# SchemaPCB1.net
KiCad netlist of a schematic drawn in EAGLE
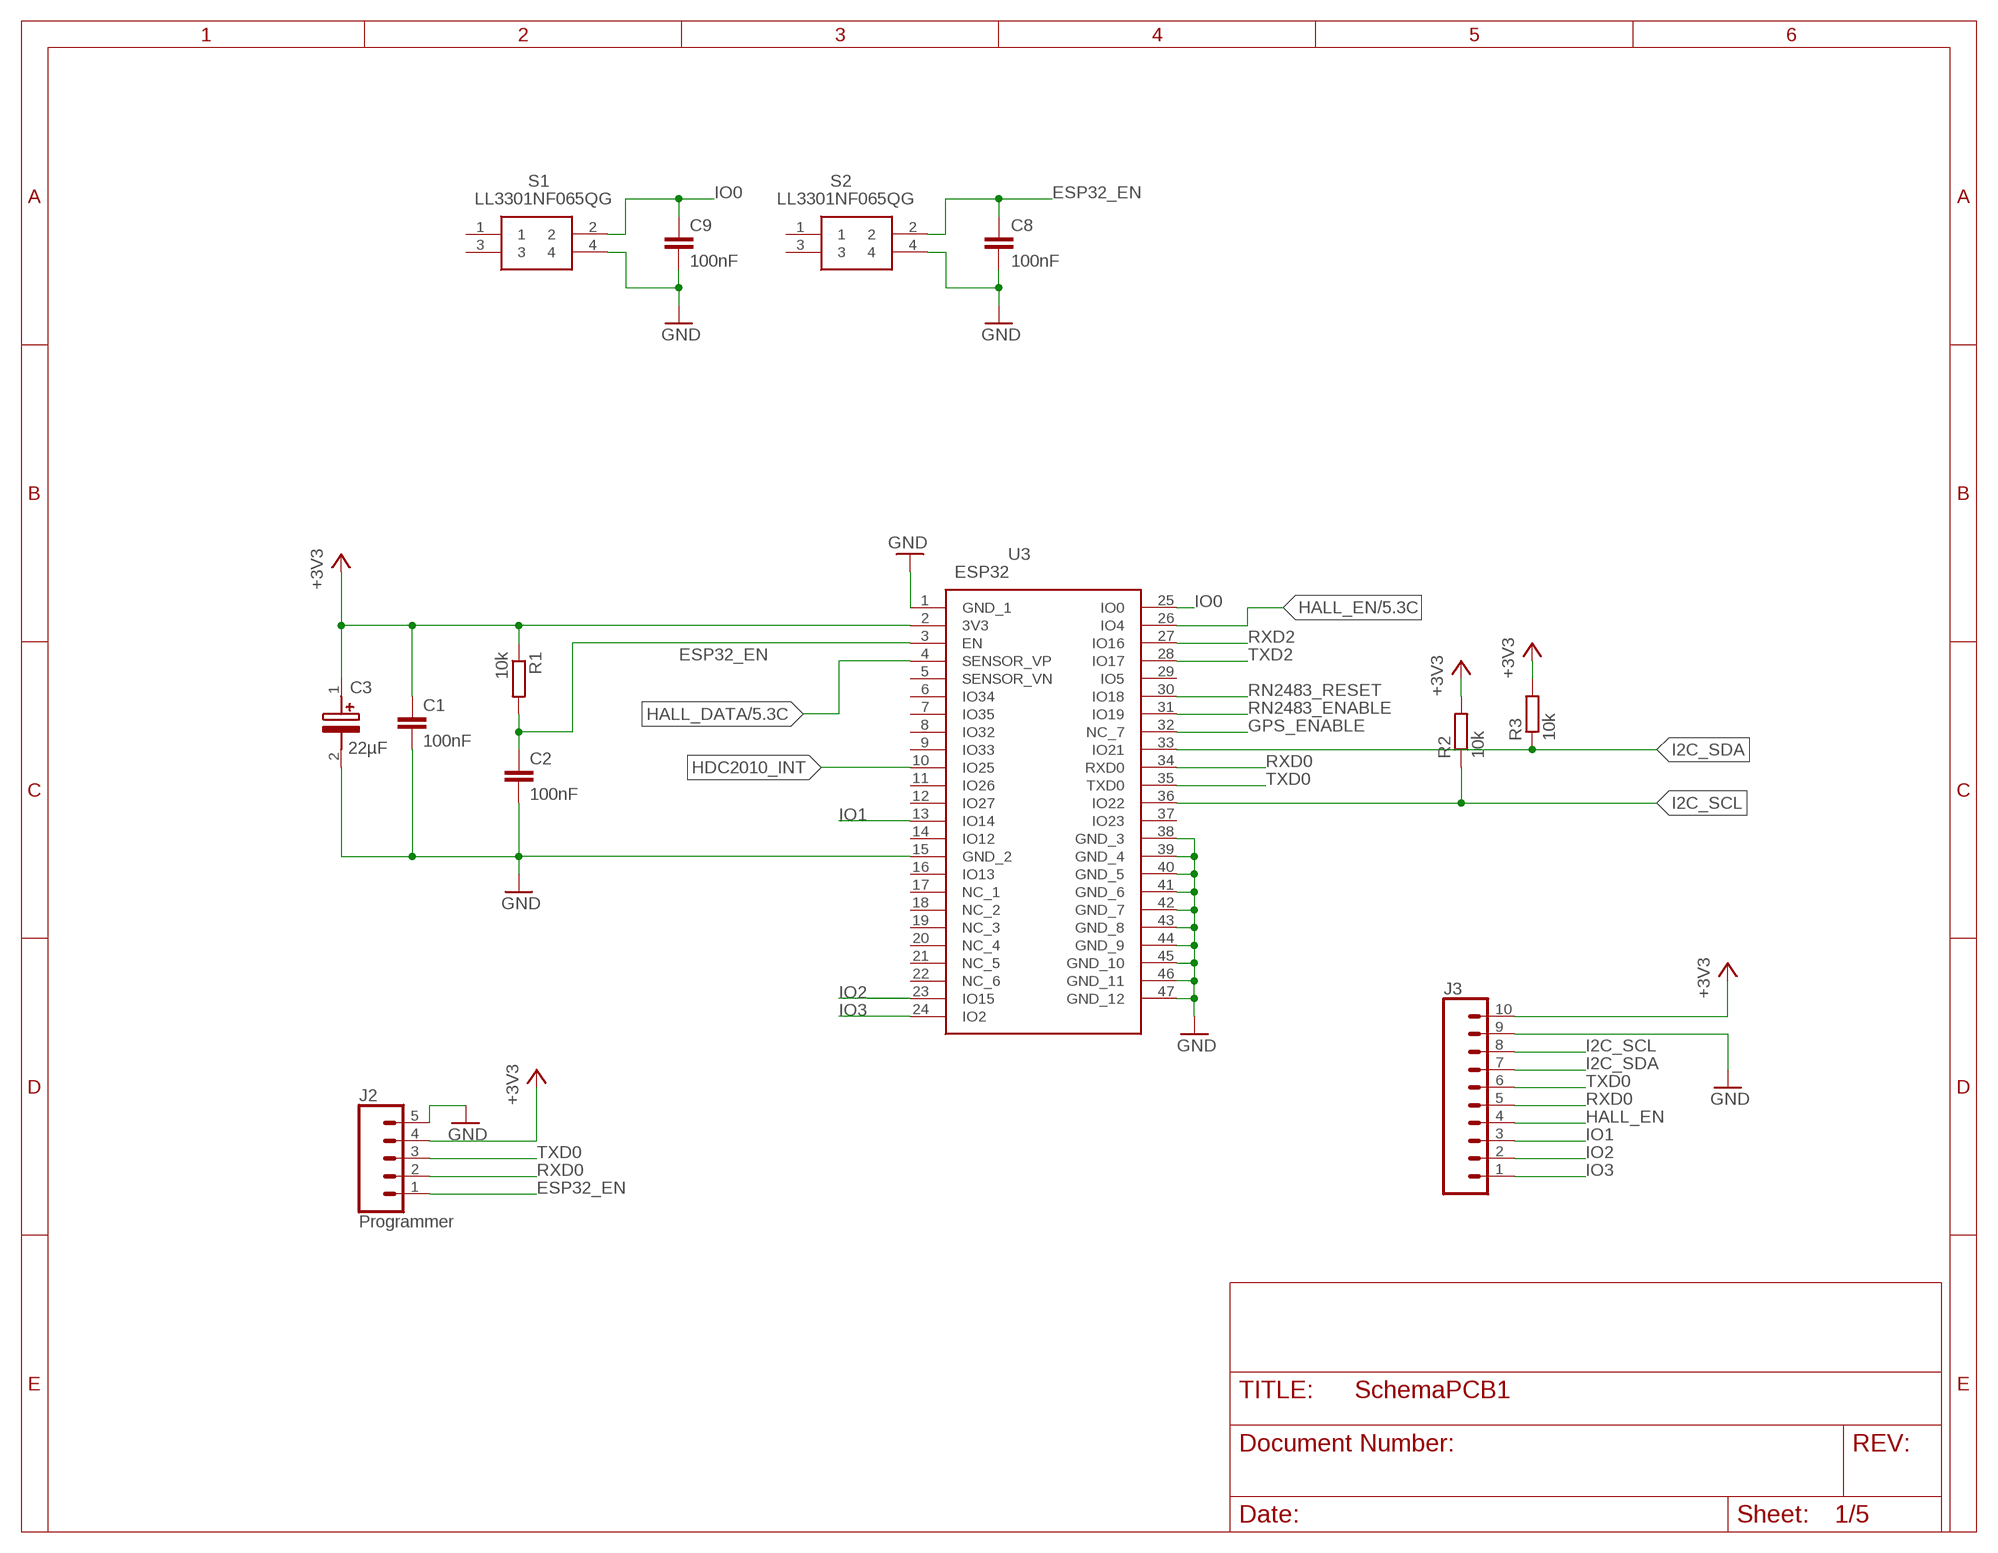
[diagram p0: schematic, sheet 1]
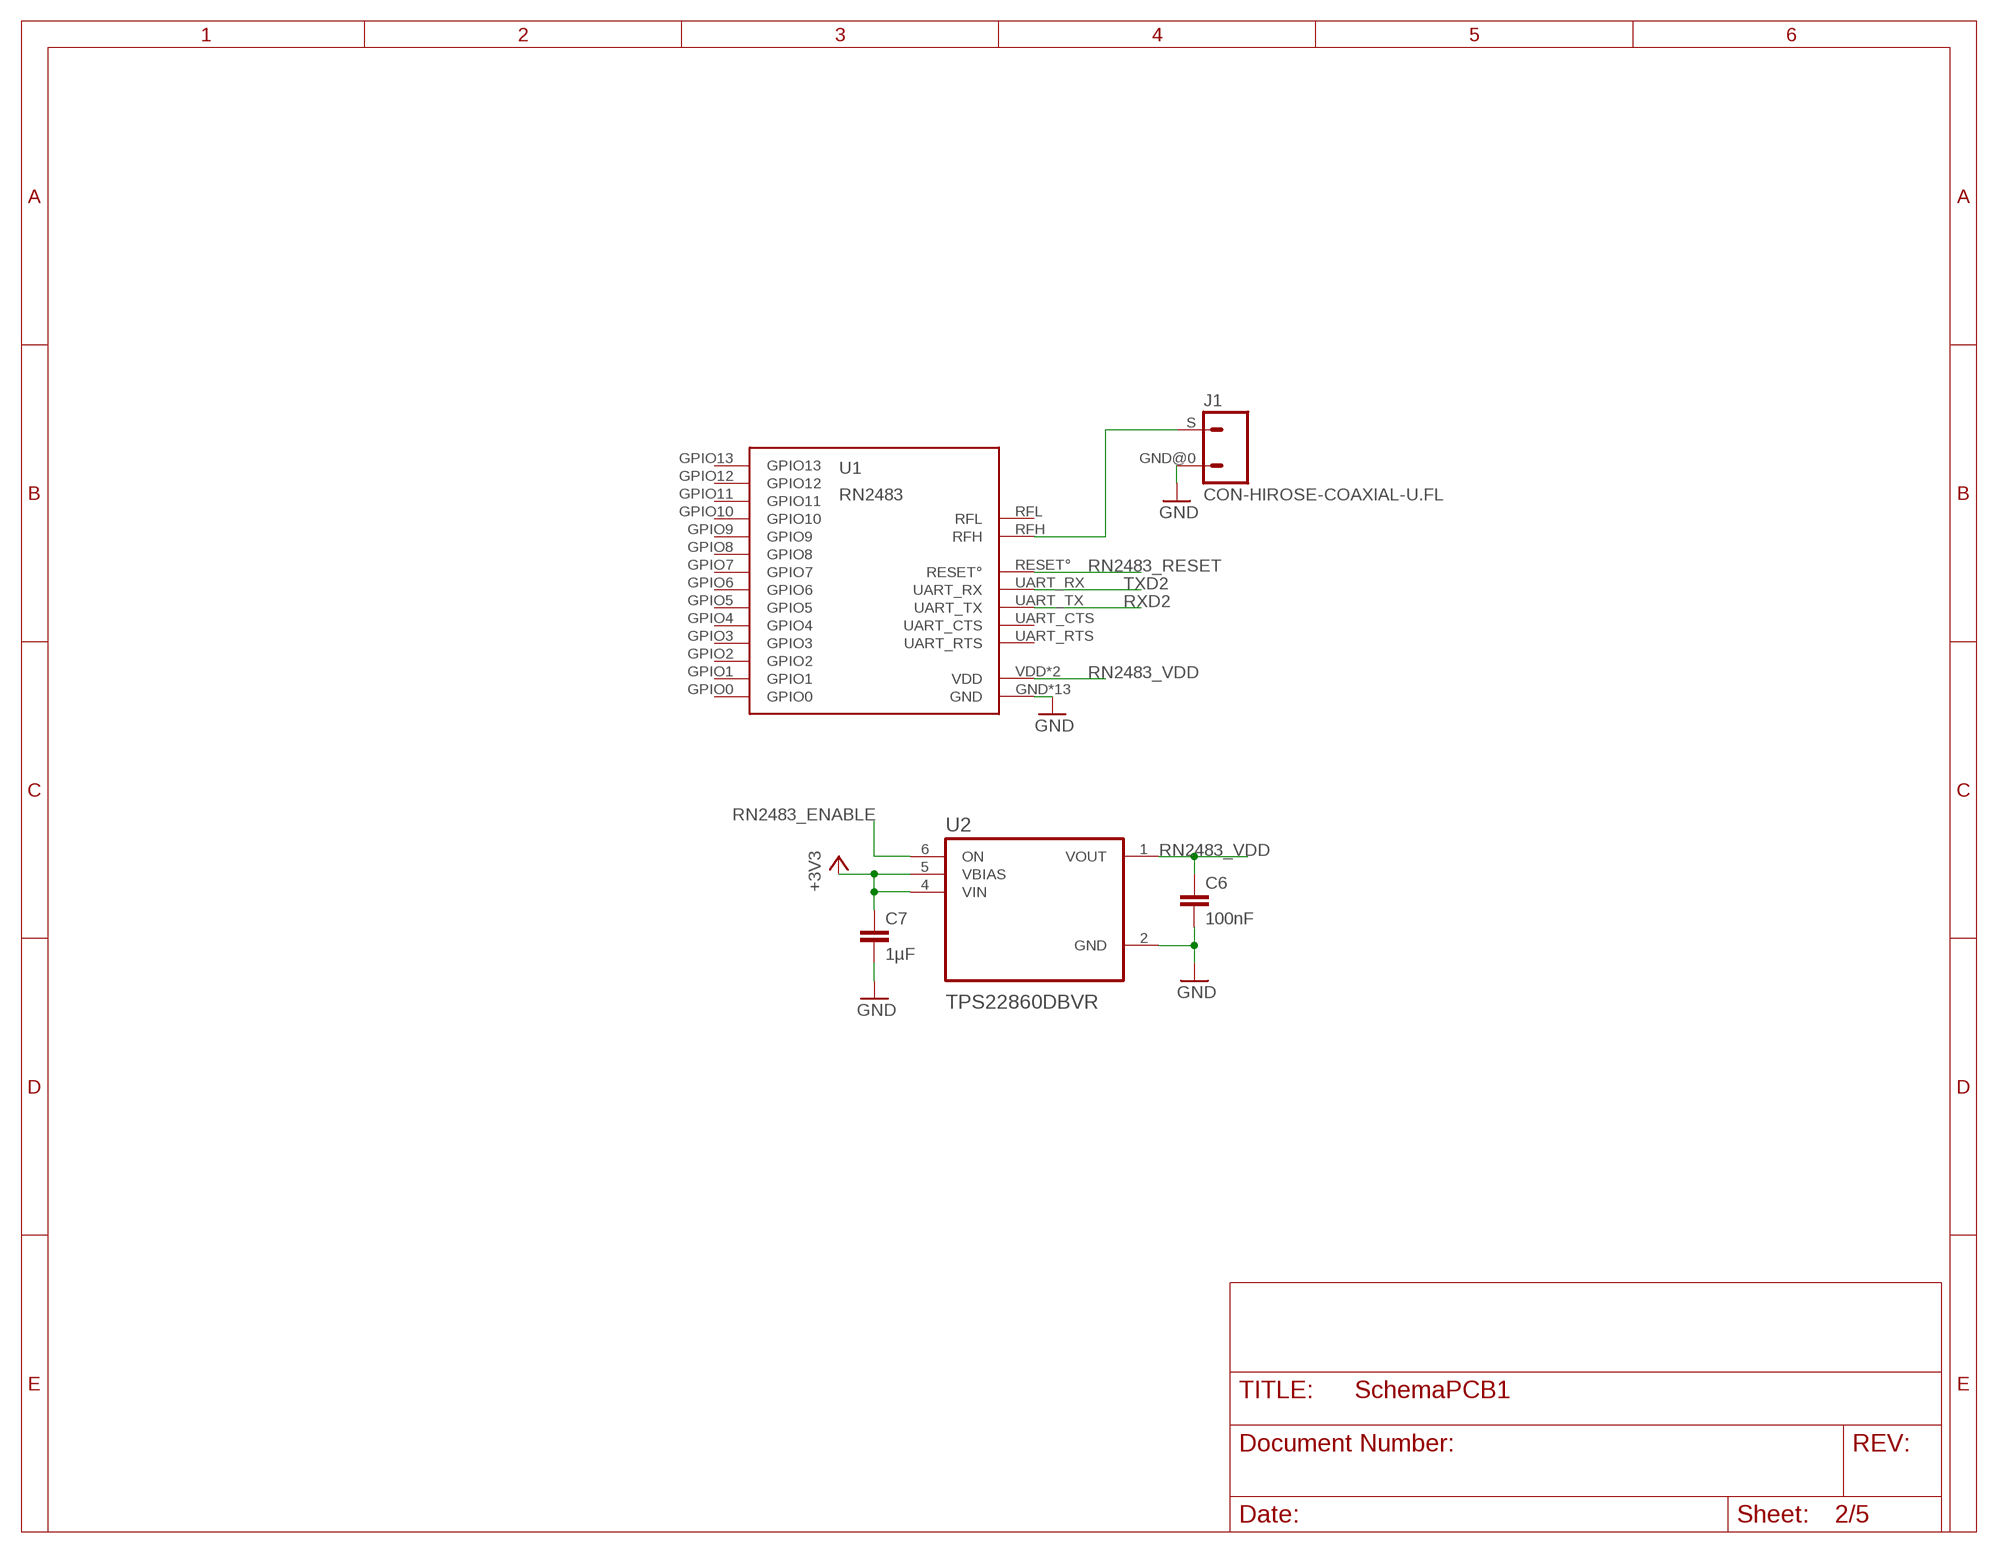
[diagram p1: schematic, sheet 2]
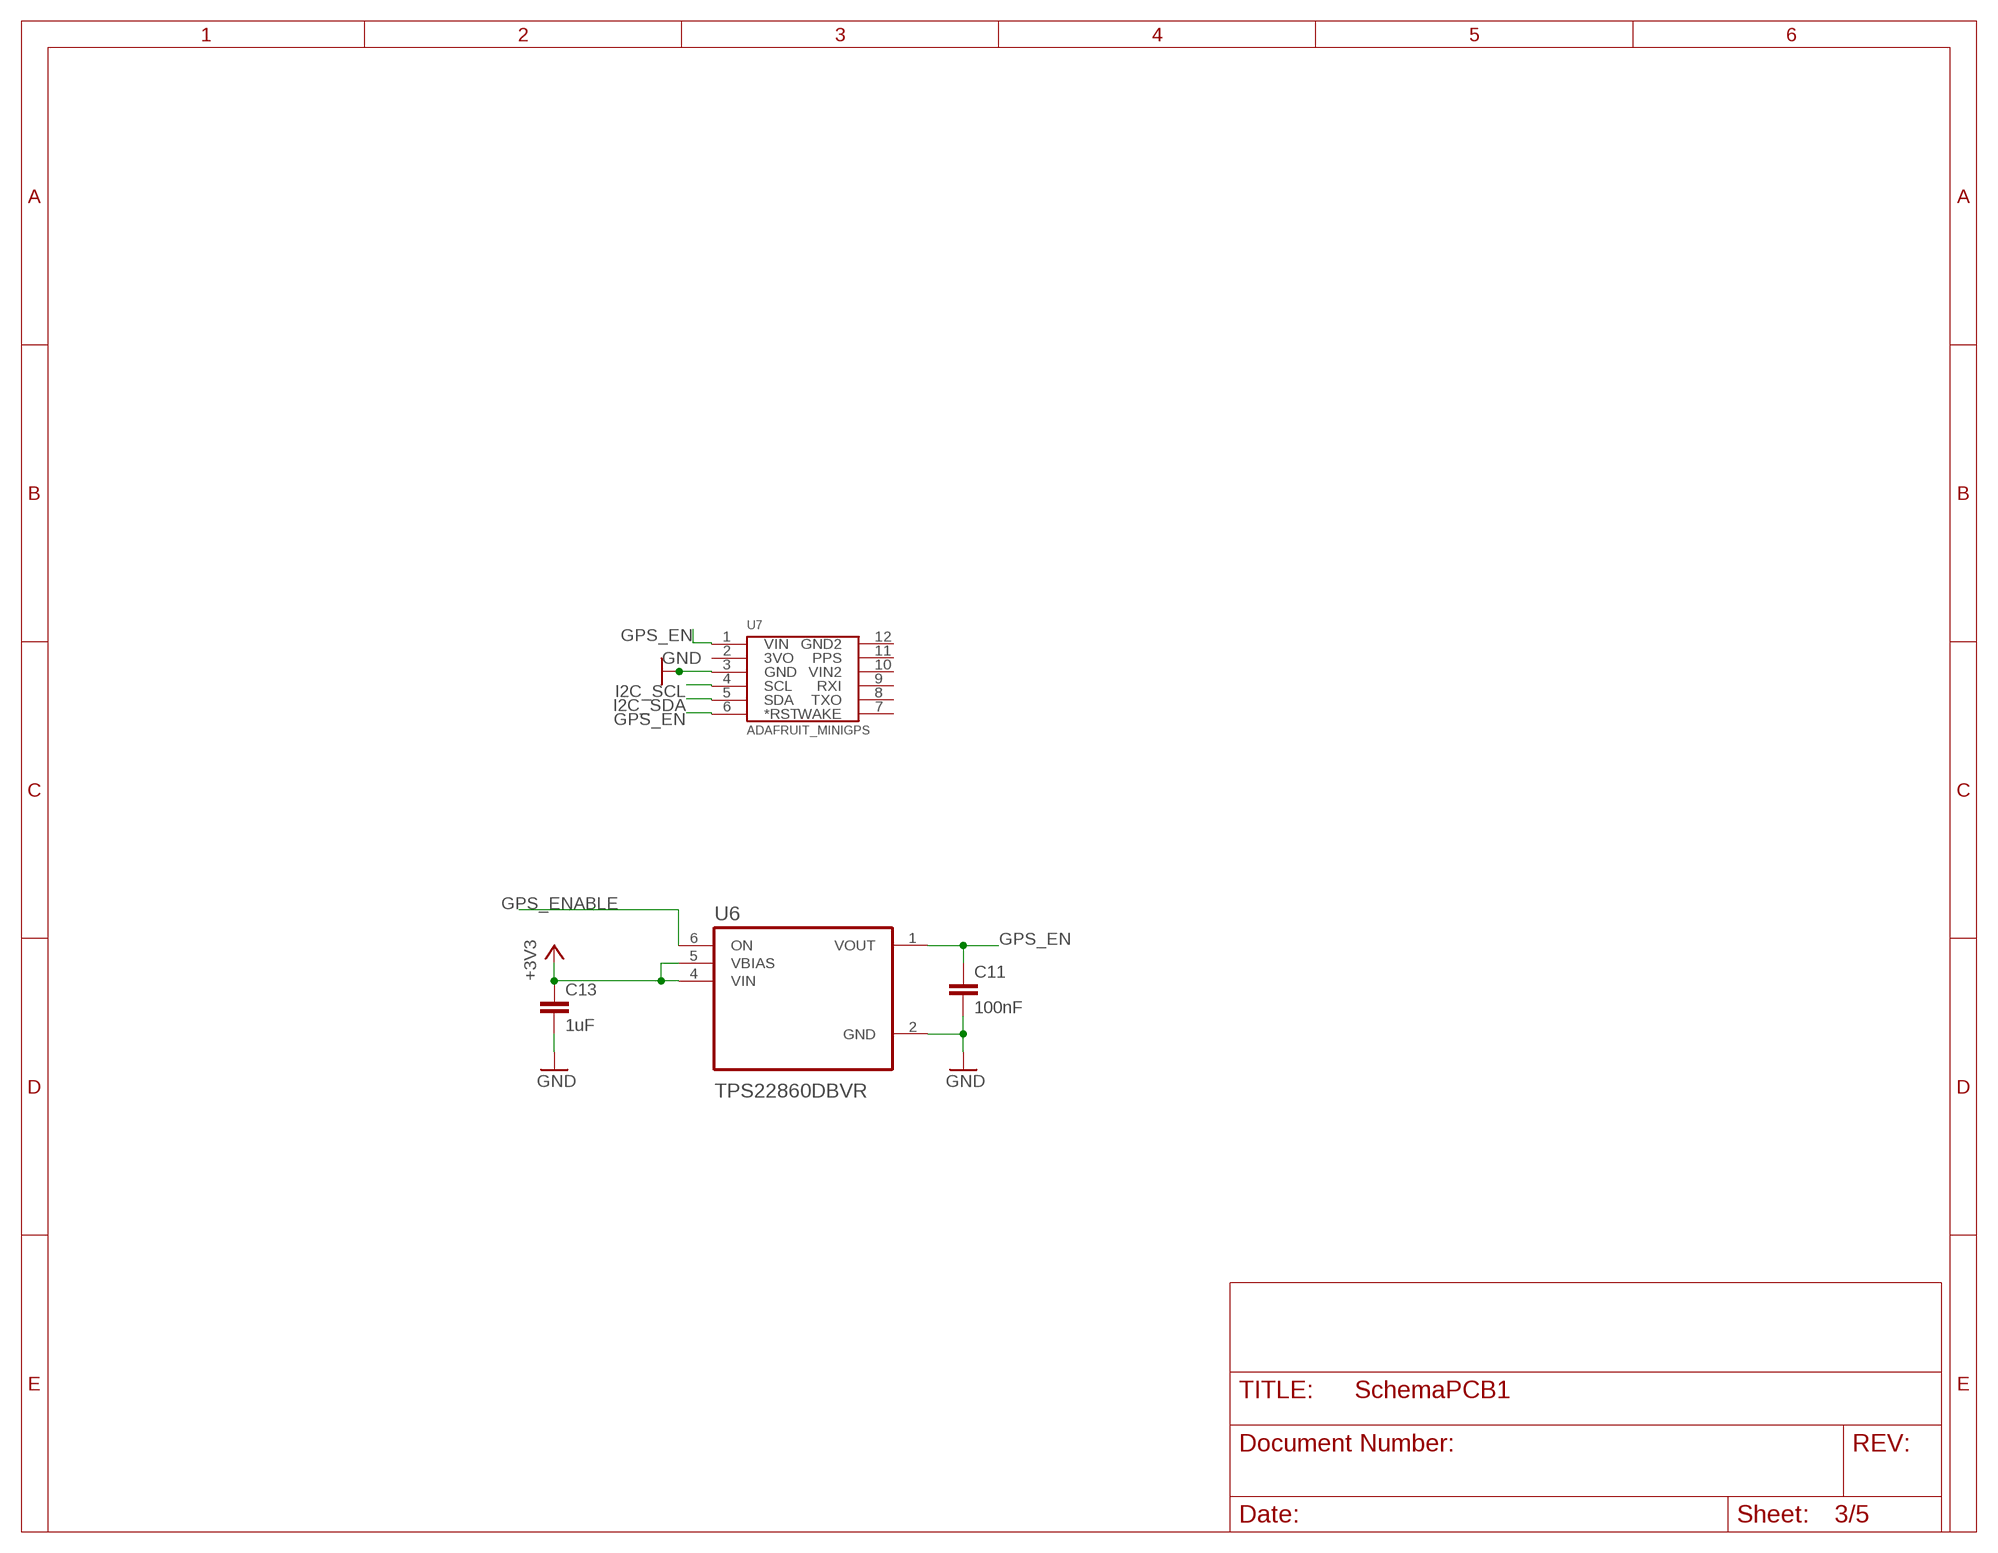
[diagram p2: schematic, sheet 3]
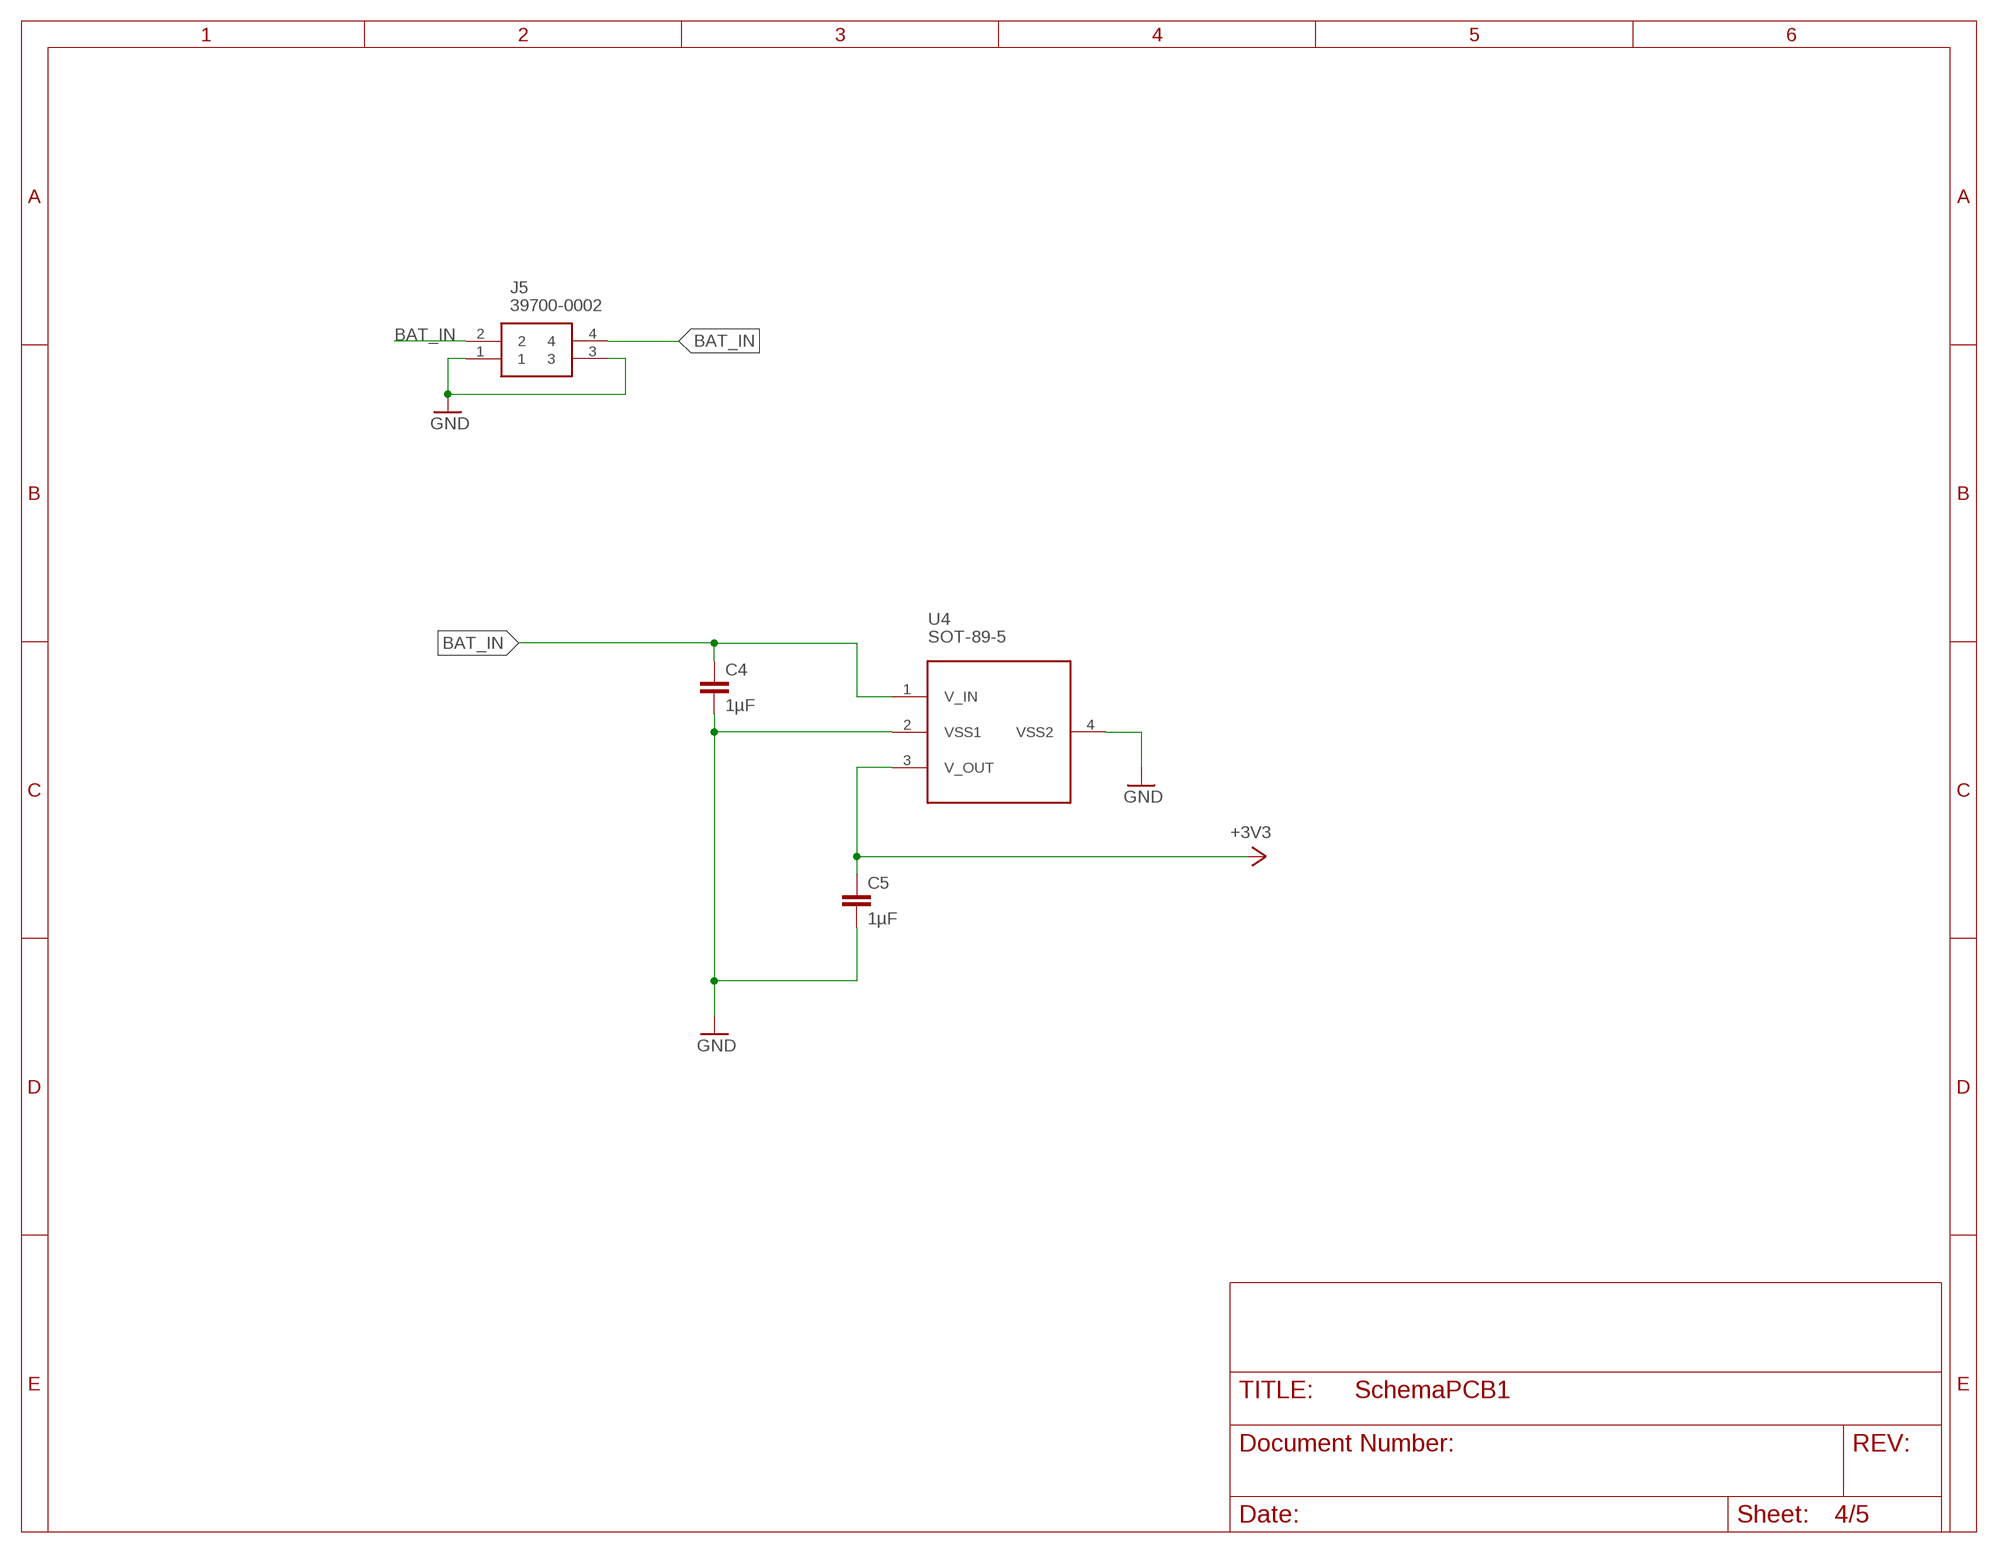
[diagram p3: schematic, sheet 4]
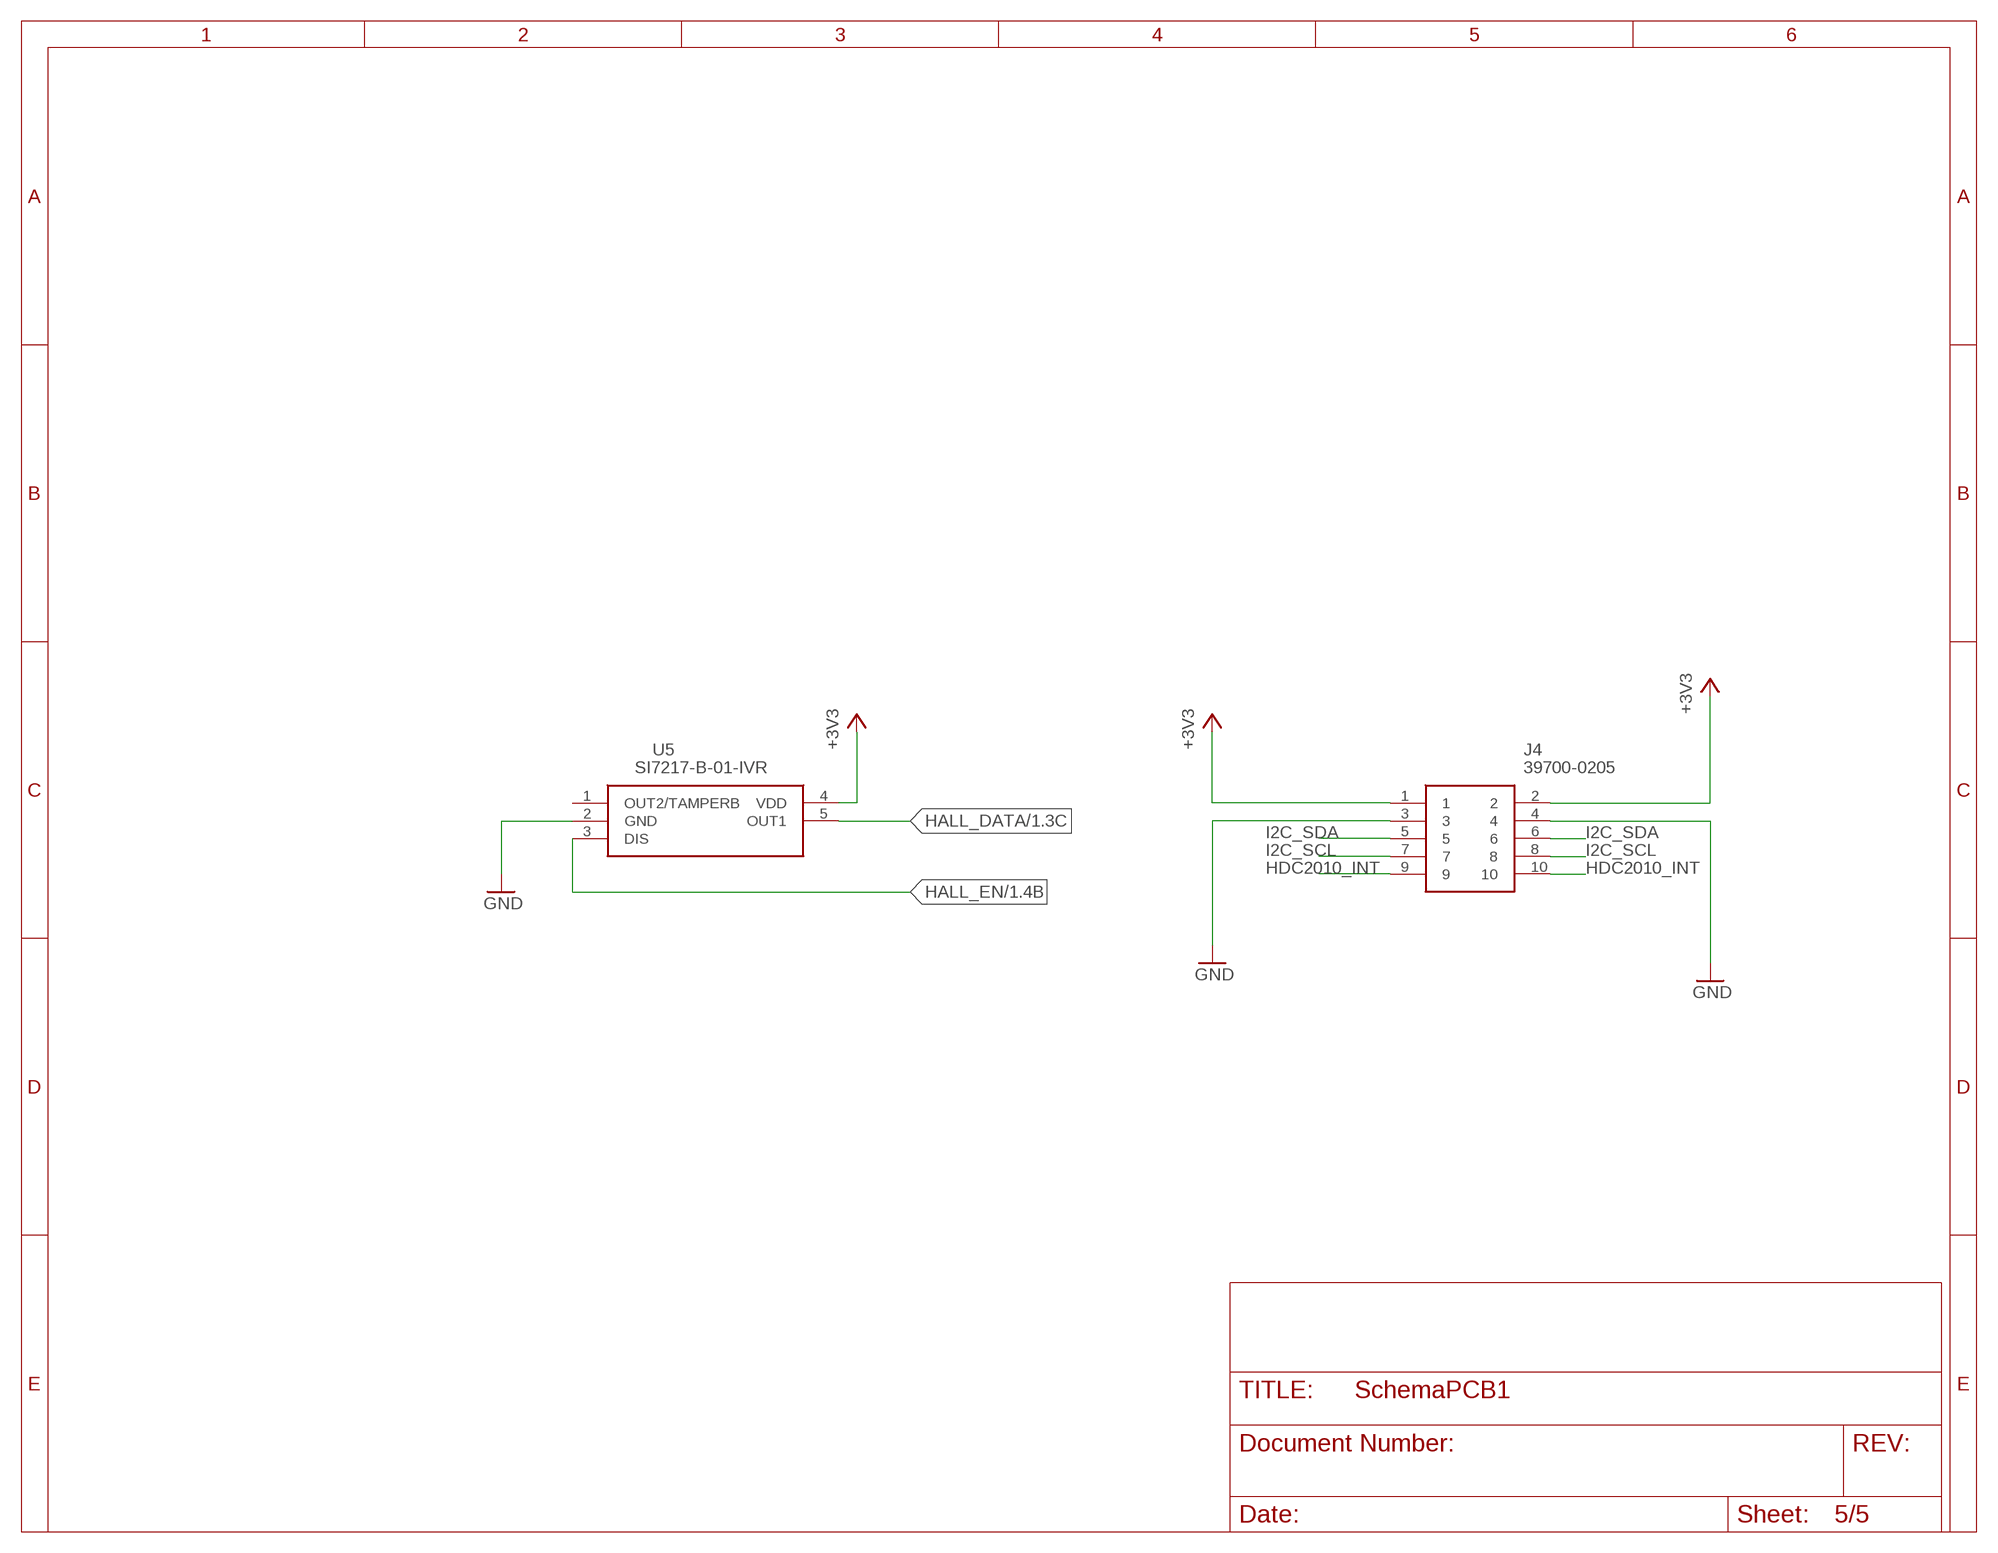
[diagram p4: schematic, sheet 5]

(export (version "E")
  (design (tool "Eeschema 10.0.6"))
  (components
    (comp (ref "J4")
      (value "39700-0205")
      (footprint "eagle-import:397000205")
      (fields (field (name "MOUSER_PART_NUMBER") "538-39700-0205"))
      (libsource (lib "eagle-import") (part "39700-0205"))
    )
    (comp (ref "U5")
      (value "SI7217-B-01-IVR")
      (footprint "eagle-import:SOT95P275X125-5N")
      (fields
        (field (name "MANUFACTURER_PART_NUMBER") "Si7217-B-01-IVR")
        (field (name "MOUSER_PART_NUMBER") "634-SI7217-B-01-IVR")
      )
      (libsource (lib "eagle-import") (part "SI7217-B-01-IVR"))
    )
    (comp (ref "C1")
      (value "100nF")
      (footprint "eagle-import:C0805")
      (libsource (lib "eagle-import") (part "C-EU-0805C0805"))
    )
    (comp (ref "C2")
      (value "100nF")
      (footprint "eagle-import:C0805")
      (libsource (lib "eagle-import") (part "C-EU-0805C0805"))
    )
    (comp (ref "C3")
      (value "22µF")
      (footprint "eagle-import:CAPAE660X550N")
      (fields
        (field (name "MANUFACTURER_PART_NUMBER") "VE-220M1VTR-0605")
        (field (name "MOUSER_PART_NUMBER") "140-VE220M1VTR0605")
      )
      (libsource (lib "eagle-import") (part "VE-220M1VTR-0605"))
    )
    (comp (ref "C8")
      (value "100nF")
      (footprint "eagle-import:C0805")
      (libsource (lib "eagle-import") (part "C-EU-0805C0805"))
    )
    (comp (ref "C9")
      (value "100nF")
      (footprint "eagle-import:C0805")
      (libsource (lib "eagle-import") (part "C-EU-0805C0805"))
    )
    (comp (ref "J2")
      (value "Programmer")
      (footprint "eagle-import:1X05")
      (libsource (lib "eagle-import") (part "CONN_05"))
    )
    (comp (ref "J3")
      (value "CONN_10\"")
      (footprint "eagle-import:1X10")
      (libsource (lib "eagle-import") (part "CONN_10{dblquote}"))
    )
    (comp (ref "R1")
      (value "10k")
      (footprint "eagle-import:M0805")
      (libsource (lib "eagle-import") (part "R-EU_0805M0805"))
    )
    (comp (ref "R2")
      (value "10k")
      (footprint "eagle-import:R0805")
      (libsource (lib "eagle-import") (part "R-EU_R0805"))
    )
    (comp (ref "R3")
      (value "10k")
      (footprint "eagle-import:R0805")
      (libsource (lib "eagle-import") (part "R-EU_R0805"))
    )
    (comp (ref "S1")
      (value "LL3301NF065QG")
      (footprint "eagle-import:LL3301NF065QG")
      (fields (field (name "MOUSER_PART_NUMBER") "612-LL3301NF065QG"))
      (libsource (lib "eagle-import") (part "LL3301NF065QG"))
    )
    (comp (ref "S2")
      (value "LL3301NF065QG")
      (footprint "eagle-import:LL3301NF065QG")
      (fields (field (name "MOUSER_PART_NUMBER") "612-LL3301NF065QG"))
      (libsource (lib "eagle-import") (part "LL3301NF065QG"))
    )
    (comp (ref "U3")
      (value "ESP32")
      (footprint "eagle-import:ESP32WROOM32EM113EH3200PH3Q0")
      (fields
        (field (name "MANUFACTURER_PART_NUMBER") "ESP32-WROOM-32E(M113EH3200PH3Q0)")
        (field (name "MOUSER_PART_NUMBER") "356-ESP32WRM32E132PH")
      )
      (libsource (lib "eagle-import") (part "ESP32-WROOM-32E_M113EH3200PH3Q"))
    )
    (comp (ref "C6")
      (value "100nF")
      (footprint "eagle-import:C0805")
      (libsource (lib "eagle-import") (part "C-EU-0805C0805"))
    )
    (comp (ref "C7")
      (value "1µF")
      (footprint "eagle-import:C0805")
      (libsource (lib "eagle-import") (part "C-EU-0805C0805"))
    )
    (comp (ref "J1")
      (value "CON-HIROSE-COAXIAL-U.FL")
      (footprint "eagle-import:CON-U.FL")
      (libsource (lib "eagle-import") (part "CON-HIROSE-COAXIAL-U.FL"))
    )
    (comp (ref "U1")
      (value "RN2483")
      (footprint "eagle-import:RN2483")
      (libsource (lib "eagle-import") (part "RN2483"))
    )
    (comp (ref "U2")
      (value "TPS22860DBVR")
      (footprint "eagle-import:SOT95P280X145-6N")
      (fields (field (name "MF") "Texas Instruments"))
      (libsource (lib "eagle-import") (part "--TPS22860DBVR_TPS22860DBVR"))
    )
    (comp (ref "C4")
      (value "1µF")
      (footprint "eagle-import:C0805")
      (libsource (lib "eagle-import") (part "C-EU-0805C0805"))
    )
    (comp (ref "C5")
      (value "1µF")
      (footprint "eagle-import:C0805")
      (libsource (lib "eagle-import") (part "C-EU-0805C0805"))
    )
    (comp (ref "J5")
      (value "39700-0002")
      (footprint "eagle-import:397000002")
      (fields (field (name "MOUSER_PART_NUMBER") "538-39700-0002"))
      (libsource (lib "eagle-import") (part "39700-0002"))
    )
    (comp (ref "U4")
      (value "SOT-89-5")
      (footprint "eagle-import:SOT-89")
      (libsource (lib "eagle-import") (part "SOT-89-5"))
    )
    (comp (ref "C11")
      (value "100nF")
      (footprint "eagle-import:C0805")
      (libsource (lib "eagle-import") (part "C-EUC0805"))
    )
    (comp (ref "C13")
      (value "1uF")
      (footprint "eagle-import:C0805")
      (libsource (lib "eagle-import") (part "C-EUC0805"))
    )
    (comp (ref "U6")
      (value "TPS22860DBVR")
      (footprint "eagle-import:SOT95P280X145-6N")
      (fields (field (name "MF") "Texas Instruments"))
      (libsource (lib "eagle-import") (part "TPS22860DBVR"))
    )
    (comp (ref "U7")
      (value "ADAFRUIT_MINIGPS")
      (footprint "eagle-import:ADAFRUIT_MINIGPS")
      (libsource (lib "eagle-import") (part "ADAFRUIT_MINIGPS"))
    )
  )
  (nets
    (net (code "1") (name "+3V3") (class "Default")
      (node (ref "C1") (pin "1") (pinfunction "1_1") (pintype "passive"))
      (node (ref "C13") (pin "1") (pinfunction "1_1") (pintype "passive"))
      (node (ref "C3") (pin "1") (pinfunction "+_1") (pintype "bidirectional"))
      (node (ref "C5") (pin "1") (pinfunction "1_1") (pintype "passive"))
      (node (ref "C7") (pin "1") (pinfunction "1_1") (pintype "passive"))
      (node (ref "J2") (pin "4") (pinfunction "4_4") (pintype "passive"))
      (node (ref "J3") (pin "10") (pinfunction "10_10") (pintype "passive"))
      (node (ref "J4") (pin "1") (pinfunction "1_1") (pintype "bidirectional"))
      (node (ref "J4") (pin "2") (pinfunction "2_2") (pintype "bidirectional"))
      (node (ref "R1") (pin "1") (pinfunction "1_1") (pintype "passive"))
      (node (ref "R2") (pin "2") (pinfunction "2_2") (pintype "passive"))
      (node (ref "R3") (pin "2") (pinfunction "2_2") (pintype "passive"))
      (node (ref "U2") (pin "4") (pinfunction "VIN_4") (pintype "input"))
      (node (ref "U2") (pin "5") (pinfunction "VBIAS_5") (pintype "input"))
      (node (ref "U3") (pin "2") (pinfunction "3V3_2") (pintype "bidirectional"))
      (node (ref "U4") (pin "3") (pinfunction "V_OUT_3") (pintype "bidirectional"))
      (node (ref "U5") (pin "4") (pinfunction "VDD_4") (pintype "bidirectional"))
      (node (ref "U6") (pin "4") (pinfunction "VIN_4") (pintype "input"))
      (node (ref "U6") (pin "5") (pinfunction "VBIAS_5") (pintype "input"))
    )
    (net (code "2") (name "BAT_IN") (class "Default")
      (node (ref "C4") (pin "1") (pinfunction "1_1") (pintype "passive"))
      (node (ref "J5") (pin "2") (pinfunction "2_2") (pintype "bidirectional"))
      (node (ref "J5") (pin "4") (pinfunction "4_4") (pintype "bidirectional"))
      (node (ref "U4") (pin "1") (pinfunction "V_IN_1") (pintype "bidirectional"))
    )
    (net (code "3") (name "ESP32_EN") (class "Default")
      (node (ref "C2") (pin "1") (pinfunction "1_1") (pintype "passive"))
      (node (ref "C8") (pin "2") (pinfunction "2_2") (pintype "passive"))
      (node (ref "J2") (pin "1") (pinfunction "1_1") (pintype "passive"))
      (node (ref "R1") (pin "2") (pinfunction "2_2") (pintype "passive"))
      (node (ref "S2") (pin "2") (pinfunction "2_2") (pintype "bidirectional"))
      (node (ref "U3") (pin "3") (pinfunction "EN_3") (pintype "bidirectional"))
    )
    (net (code "4") (name "GND") (class "Default")
      (node (ref "C1") (pin "2") (pinfunction "2_2") (pintype "passive"))
      (node (ref "C11") (pin "2") (pinfunction "2_2") (pintype "passive"))
      (node (ref "C13") (pin "2") (pinfunction "2_2") (pintype "passive"))
      (node (ref "C2") (pin "2") (pinfunction "2_2") (pintype "passive"))
      (node (ref "C3") (pin "2") (pinfunction "-_2") (pintype "bidirectional"))
      (node (ref "C4") (pin "2") (pinfunction "2_2") (pintype "passive"))
      (node (ref "C5") (pin "2") (pinfunction "2_2") (pintype "passive"))
      (node (ref "C6") (pin "2") (pinfunction "2_2") (pintype "passive"))
      (node (ref "C7") (pin "2") (pinfunction "2_2") (pintype "passive"))
      (node (ref "C8") (pin "1") (pinfunction "1_1") (pintype "passive"))
      (node (ref "C9") (pin "2") (pinfunction "2_2") (pintype "passive"))
      (node (ref "J1") (pin "GND@0") (pinfunction "2_GND@0") (pintype "passive"))
      (node (ref "J2") (pin "5") (pinfunction "5_5") (pintype "passive"))
      (node (ref "J3") (pin "9") (pinfunction "9_9") (pintype "passive"))
      (node (ref "J4") (pin "3") (pinfunction "3_3") (pintype "bidirectional"))
      (node (ref "J4") (pin "4") (pinfunction "4_4") (pintype "bidirectional"))
      (node (ref "J5") (pin "1") (pinfunction "1_1") (pintype "bidirectional"))
      (node (ref "J5") (pin "3") (pinfunction "3_3") (pintype "bidirectional"))
      (node (ref "S1") (pin "4") (pinfunction "4_4") (pintype "bidirectional"))
      (node (ref "S2") (pin "4") (pinfunction "4_4") (pintype "bidirectional"))
      (node (ref "U1") (pin "GND") (pinfunction "GND_GND") (pintype "bidirectional"))
      (node (ref "U1") (pin "GND1") (pinfunction "GND_GND1") (pintype "bidirectional"))
      (node (ref "U1") (pin "GND10") (pinfunction "GND_GND10") (pintype "bidirectional"))
      (node (ref "U1") (pin "GND11") (pinfunction "GND_GND11") (pintype "bidirectional"))
      (node (ref "U1") (pin "GND12") (pinfunction "GND_GND12") (pintype "bidirectional"))
      (node (ref "U1") (pin "GND2") (pinfunction "GND_GND2") (pintype "bidirectional"))
      (node (ref "U1") (pin "GND3") (pinfunction "GND_GND3") (pintype "bidirectional"))
      (node (ref "U1") (pin "GND4") (pinfunction "GND_GND4") (pintype "bidirectional"))
      (node (ref "U1") (pin "GND5") (pinfunction "GND_GND5") (pintype "bidirectional"))
      (node (ref "U1") (pin "GND6") (pinfunction "GND_GND6") (pintype "bidirectional"))
      (node (ref "U1") (pin "GND7") (pinfunction "GND_GND7") (pintype "bidirectional"))
      (node (ref "U1") (pin "GND8") (pinfunction "GND_GND8") (pintype "bidirectional"))
      (node (ref "U1") (pin "GND9") (pinfunction "GND_GND9") (pintype "bidirectional"))
      (node (ref "U2") (pin "2") (pinfunction "GND_2") (pintype "power_in"))
      (node (ref "U3") (pin "1") (pinfunction "GND_1_1") (pintype "bidirectional"))
      (node (ref "U3") (pin "15") (pinfunction "GND_2_15") (pintype "bidirectional"))
      (node (ref "U3") (pin "38") (pinfunction "GND_3_38") (pintype "bidirectional"))
      (node (ref "U3") (pin "39") (pinfunction "GND_4_39") (pintype "bidirectional"))
      (node (ref "U3") (pin "40") (pinfunction "GND_5_40") (pintype "bidirectional"))
      (node (ref "U3") (pin "41") (pinfunction "GND_6_41") (pintype "bidirectional"))
      (node (ref "U3") (pin "42") (pinfunction "GND_7_42") (pintype "bidirectional"))
      (node (ref "U3") (pin "43") (pinfunction "GND_8_43") (pintype "bidirectional"))
      (node (ref "U3") (pin "44") (pinfunction "GND_9_44") (pintype "bidirectional"))
      (node (ref "U3") (pin "45") (pinfunction "GND_10_45") (pintype "bidirectional"))
      (node (ref "U3") (pin "46") (pinfunction "GND_11_46") (pintype "bidirectional"))
      (node (ref "U3") (pin "47") (pinfunction "GND_12_47") (pintype "bidirectional"))
      (node (ref "U4") (pin "2") (pinfunction "VSS1_2") (pintype "bidirectional"))
      (node (ref "U4") (pin "4") (pinfunction "VSS2_4") (pintype "bidirectional"))
      (node (ref "U5") (pin "2") (pinfunction "GND_2") (pintype "bidirectional"))
      (node (ref "U6") (pin "2") (pinfunction "GND_2") (pintype "power_in"))
      (node (ref "U7") (pin "3") (pinfunction "GND_3") (pintype "bidirectional"))
    )
    (net (code "5") (name "GPS_EN") (class "Default")
      (node (ref "C11") (pin "1") (pinfunction "1_1") (pintype "passive"))
      (node (ref "U6") (pin "1") (pinfunction "VOUT_1") (pintype "output"))
      (node (ref "U7") (pin "1") (pinfunction "VIN_1") (pintype "bidirectional"))
      (node (ref "U7") (pin "6") (pinfunction "*RST_6") (pintype "bidirectional"))
    )
    (net (code "6") (name "GPS_ENABLE") (class "Default")
      (node (ref "U3") (pin "32") (pinfunction "NC_7_32") (pintype "bidirectional"))
      (node (ref "U6") (pin "6") (pinfunction "ON_6") (pintype "input"))
    )
    (net (code "7") (name "HALL_DATA") (class "Default")
      (node (ref "U3") (pin "4") (pinfunction "SENSOR_VP_4") (pintype "bidirectional"))
      (node (ref "U5") (pin "5") (pinfunction "OUT1_5") (pintype "bidirectional"))
    )
    (net (code "8") (name "HALL_EN") (class "Default")
      (node (ref "J3") (pin "4") (pinfunction "4_4") (pintype "passive"))
      (node (ref "U3") (pin "26") (pinfunction "IO4_26") (pintype "bidirectional"))
      (node (ref "U5") (pin "3") (pinfunction "DIS_3") (pintype "bidirectional"))
    )
    (net (code "9") (name "HDC2010_INT") (class "Default")
      (node (ref "J4") (pin "10") (pinfunction "10_10") (pintype "bidirectional"))
      (node (ref "J4") (pin "9") (pinfunction "9_9") (pintype "bidirectional"))
      (node (ref "U3") (pin "10") (pinfunction "IO25_10") (pintype "bidirectional"))
    )
    (net (code "10") (name "I2C_SCL") (class "Default")
      (node (ref "J3") (pin "8") (pinfunction "8_8") (pintype "passive"))
      (node (ref "J4") (pin "7") (pinfunction "7_7") (pintype "bidirectional"))
      (node (ref "J4") (pin "8") (pinfunction "8_8") (pintype "bidirectional"))
      (node (ref "R2") (pin "1") (pinfunction "1_1") (pintype "passive"))
      (node (ref "U3") (pin "36") (pinfunction "IO22_36") (pintype "bidirectional"))
      (node (ref "U7") (pin "4") (pinfunction "SCL_4") (pintype "bidirectional"))
    )
    (net (code "11") (name "I2C_SDA") (class "Default")
      (node (ref "J3") (pin "7") (pinfunction "7_7") (pintype "passive"))
      (node (ref "J4") (pin "5") (pinfunction "5_5") (pintype "bidirectional"))
      (node (ref "J4") (pin "6") (pinfunction "6_6") (pintype "bidirectional"))
      (node (ref "R3") (pin "1") (pinfunction "1_1") (pintype "passive"))
      (node (ref "U3") (pin "33") (pinfunction "IO21_33") (pintype "bidirectional"))
      (node (ref "U7") (pin "5") (pinfunction "SDA_5") (pintype "bidirectional"))
    )
    (net (code "12") (name "IO0") (class "Default")
      (node (ref "C9") (pin "1") (pinfunction "1_1") (pintype "passive"))
      (node (ref "S1") (pin "2") (pinfunction "2_2") (pintype "bidirectional"))
      (node (ref "U3") (pin "25") (pinfunction "IO0_25") (pintype "bidirectional"))
    )
    (net (code "13") (name "IO1") (class "Default")
      (node (ref "J3") (pin "3") (pinfunction "3_3") (pintype "passive"))
      (node (ref "U3") (pin "13") (pinfunction "IO14_13") (pintype "bidirectional"))
    )
    (net (code "14") (name "IO2") (class "Default")
      (node (ref "J3") (pin "2") (pinfunction "2_2") (pintype "passive"))
      (node (ref "U3") (pin "23") (pinfunction "IO15_23") (pintype "bidirectional"))
    )
    (net (code "15") (name "IO3") (class "Default")
      (node (ref "J3") (pin "1") (pinfunction "1_1") (pintype "passive"))
      (node (ref "U3") (pin "24") (pinfunction "IO2_24") (pintype "bidirectional"))
    )
    (net (code "16") (name "Net-(J1-1)") (class "Default")
      (node (ref "J1") (pin "S") (pinfunction "1_S") (pintype "passive"))
      (node (ref "U1") (pin "RFH") (pinfunction "RFH_RFH") (pintype "bidirectional"))
    )
    (net (code "17") (name "RN2483_ENABLE") (class "Default")
      (node (ref "U2") (pin "6") (pinfunction "ON_6") (pintype "input"))
      (node (ref "U3") (pin "31") (pinfunction "IO19_31") (pintype "bidirectional"))
    )
    (net (code "18") (name "RN2483_RESET") (class "Default")
      (node (ref "U1") (pin "RESET°") (pinfunction "RESET°_RESET°") (pintype "bidirectional"))
      (node (ref "U3") (pin "30") (pinfunction "IO18_30") (pintype "bidirectional"))
    )
    (net (code "19") (name "RN2483_VDD") (class "Default")
      (node (ref "C6") (pin "1") (pinfunction "1_1") (pintype "passive"))
      (node (ref "U1") (pin "VDD") (pinfunction "VDD_VDD") (pintype "bidirectional"))
      (node (ref "U1") (pin "VDD2") (pinfunction "VDD_VDD2") (pintype "bidirectional"))
      (node (ref "U2") (pin "1") (pinfunction "VOUT_1") (pintype "output"))
    )
    (net (code "20") (name "RXD0") (class "Default")
      (node (ref "J2") (pin "2") (pinfunction "2_2") (pintype "passive"))
      (node (ref "J3") (pin "5") (pinfunction "5_5") (pintype "passive"))
      (node (ref "U3") (pin "34") (pinfunction "RXD0_34") (pintype "bidirectional"))
    )
    (net (code "21") (name "RXD2") (class "Default")
      (node (ref "U1") (pin "UART_TX") (pinfunction "UART_TX_UART_TX") (pintype "bidirectional"))
      (node (ref "U3") (pin "27") (pinfunction "IO16_27") (pintype "bidirectional"))
    )
    (net (code "22") (name "TXD0") (class "Default")
      (node (ref "J2") (pin "3") (pinfunction "3_3") (pintype "passive"))
      (node (ref "J3") (pin "6") (pinfunction "6_6") (pintype "passive"))
      (node (ref "U3") (pin "35") (pinfunction "TXD0_35") (pintype "bidirectional"))
    )
    (net (code "23") (name "TXD2") (class "Default")
      (node (ref "U1") (pin "UART_RX") (pinfunction "UART_RX_UART_RX") (pintype "bidirectional"))
      (node (ref "U3") (pin "28") (pinfunction "IO17_28") (pintype "bidirectional"))
    )
    (net (code "24") (name "unconnected-(S1-Pad1)") (class "Default")
      (node (ref "S1") (pin "1") (pinfunction "1_1") (pintype "bidirectional"))
    )
    (net (code "25") (name "unconnected-(S1-Pad3)") (class "Default")
      (node (ref "S1") (pin "3") (pinfunction "3_3") (pintype "bidirectional"))
    )
    (net (code "26") (name "unconnected-(S2-Pad1)") (class "Default")
      (node (ref "S2") (pin "1") (pinfunction "1_1") (pintype "bidirectional"))
    )
    (net (code "27") (name "unconnected-(S2-Pad3)") (class "Default")
      (node (ref "S2") (pin "3") (pinfunction "3_3") (pintype "bidirectional"))
    )
    (net (code "28") (name "unconnected-(U1-PadGPIO0)") (class "Default")
      (node (ref "U1") (pin "GPIO0") (pinfunction "GPIO0_GPIO0") (pintype "bidirectional"))
    )
    (net (code "29") (name "unconnected-(U1-PadGPIO1)") (class "Default")
      (node (ref "U1") (pin "GPIO1") (pinfunction "GPIO1_GPIO1") (pintype "bidirectional"))
    )
    (net (code "30") (name "unconnected-(U1-PadGPIO2)") (class "Default")
      (node (ref "U1") (pin "GPIO2") (pinfunction "GPIO2_GPIO2") (pintype "bidirectional"))
    )
    (net (code "31") (name "unconnected-(U1-PadGPIO3)") (class "Default")
      (node (ref "U1") (pin "GPIO3") (pinfunction "GPIO3_GPIO3") (pintype "bidirectional"))
    )
    (net (code "32") (name "unconnected-(U1-PadGPIO4)") (class "Default")
      (node (ref "U1") (pin "GPIO4") (pinfunction "GPIO4_GPIO4") (pintype "bidirectional"))
    )
    (net (code "33") (name "unconnected-(U1-PadGPIO5)") (class "Default")
      (node (ref "U1") (pin "GPIO5") (pinfunction "GPIO5_GPIO5") (pintype "bidirectional"))
    )
    (net (code "34") (name "unconnected-(U1-PadGPIO6)") (class "Default")
      (node (ref "U1") (pin "GPIO6") (pinfunction "GPIO6_GPIO6") (pintype "bidirectional"))
    )
    (net (code "35") (name "unconnected-(U1-PadGPIO7)") (class "Default")
      (node (ref "U1") (pin "GPIO7") (pinfunction "GPIO7_GPIO7") (pintype "bidirectional"))
    )
    (net (code "36") (name "unconnected-(U1-PadGPIO8)") (class "Default")
      (node (ref "U1") (pin "GPIO8") (pinfunction "GPIO8_GPIO8") (pintype "bidirectional"))
    )
    (net (code "37") (name "unconnected-(U1-PadGPIO9)") (class "Default")
      (node (ref "U1") (pin "GPIO9") (pinfunction "GPIO9_GPIO9") (pintype "bidirectional"))
    )
    (net (code "38") (name "unconnected-(U1-PadGPIO10)") (class "Default")
      (node (ref "U1") (pin "GPIO10") (pinfunction "GPIO10_GPIO10") (pintype "bidirectional"))
    )
    (net (code "39") (name "unconnected-(U1-PadGPIO11)") (class "Default")
      (node (ref "U1") (pin "GPIO11") (pinfunction "GPIO11_GPIO11") (pintype "bidirectional"))
    )
    (net (code "40") (name "unconnected-(U1-PadGPIO12)") (class "Default")
      (node (ref "U1") (pin "GPIO12") (pinfunction "GPIO12_GPIO12") (pintype "bidirectional"))
    )
    (net (code "41") (name "unconnected-(U1-PadGPIO13)") (class "Default")
      (node (ref "U1") (pin "GPIO13") (pinfunction "GPIO13_GPIO13") (pintype "bidirectional"))
    )
    (net (code "42") (name "unconnected-(U1-PadRFL)") (class "Default")
      (node (ref "U1") (pin "RFL") (pinfunction "RFL_RFL") (pintype "bidirectional"))
    )
    (net (code "43") (name "unconnected-(U1-PadUART_CTS)") (class "Default")
      (node (ref "U1") (pin "UART_CTS") (pinfunction "UART_CTS_UART_CTS") (pintype "bidirectional"))
    )
    (net (code "44") (name "unconnected-(U1-PadUART_RTS)") (class "Default")
      (node (ref "U1") (pin "UART_RTS") (pinfunction "UART_RTS_UART_RTS") (pintype "bidirectional"))
    )
    (net (code "45") (name "unconnected-(U3-IO5-Pad29)") (class "Default")
      (node (ref "U3") (pin "29") (pinfunction "IO5_29") (pintype "bidirectional"))
    )
    (net (code "46") (name "unconnected-(U3-IO12-Pad14)") (class "Default")
      (node (ref "U3") (pin "14") (pinfunction "IO12_14") (pintype "bidirectional"))
    )
    (net (code "47") (name "unconnected-(U3-IO13-Pad16)") (class "Default")
      (node (ref "U3") (pin "16") (pinfunction "IO13_16") (pintype "bidirectional"))
    )
    (net (code "48") (name "unconnected-(U3-IO23-Pad37)") (class "Default")
      (node (ref "U3") (pin "37") (pinfunction "IO23_37") (pintype "bidirectional"))
    )
    (net (code "49") (name "unconnected-(U3-IO26-Pad11)") (class "Default")
      (node (ref "U3") (pin "11") (pinfunction "IO26_11") (pintype "bidirectional"))
    )
    (net (code "50") (name "unconnected-(U3-IO27-Pad12)") (class "Default")
      (node (ref "U3") (pin "12") (pinfunction "IO27_12") (pintype "bidirectional"))
    )
    (net (code "51") (name "unconnected-(U3-IO32-Pad8)") (class "Default")
      (node (ref "U3") (pin "8") (pinfunction "IO32_8") (pintype "bidirectional"))
    )
    (net (code "52") (name "unconnected-(U3-IO33-Pad9)") (class "Default")
      (node (ref "U3") (pin "9") (pinfunction "IO33_9") (pintype "bidirectional"))
    )
    (net (code "53") (name "unconnected-(U3-IO34-Pad6)") (class "Default")
      (node (ref "U3") (pin "6") (pinfunction "IO34_6") (pintype "bidirectional"))
    )
    (net (code "54") (name "unconnected-(U3-IO35-Pad7)") (class "Default")
      (node (ref "U3") (pin "7") (pinfunction "IO35_7") (pintype "bidirectional"))
    )
    (net (code "55") (name "unconnected-(U3-NC_1-Pad17)") (class "Default")
      (node (ref "U3") (pin "17") (pinfunction "NC_1_17") (pintype "bidirectional"))
    )
    (net (code "56") (name "unconnected-(U3-NC_2-Pad18)") (class "Default")
      (node (ref "U3") (pin "18") (pinfunction "NC_2_18") (pintype "bidirectional"))
    )
    (net (code "57") (name "unconnected-(U3-NC_3-Pad19)") (class "Default")
      (node (ref "U3") (pin "19") (pinfunction "NC_3_19") (pintype "bidirectional"))
    )
    (net (code "58") (name "unconnected-(U3-NC_4-Pad20)") (class "Default")
      (node (ref "U3") (pin "20") (pinfunction "NC_4_20") (pintype "bidirectional"))
    )
    (net (code "59") (name "unconnected-(U3-NC_5-Pad21)") (class "Default")
      (node (ref "U3") (pin "21") (pinfunction "NC_5_21") (pintype "bidirectional"))
    )
    (net (code "60") (name "unconnected-(U3-NC_6-Pad22)") (class "Default")
      (node (ref "U3") (pin "22") (pinfunction "NC_6_22") (pintype "bidirectional"))
    )
    (net (code "61") (name "unconnected-(U3-SENSOR_VN-Pad5)") (class "Default")
      (node (ref "U3") (pin "5") (pinfunction "SENSOR_VN_5") (pintype "bidirectional"))
    )
    (net (code "62") (name "unconnected-(U5-OUT2{slash}TAMPERB-Pad1)") (class "Default")
      (node (ref "U5") (pin "1") (pinfunction "OUT2/TAMPERB_1") (pintype "bidirectional"))
    )
    (net (code "63") (name "unconnected-(U7-3VO-Pad2)") (class "Default")
      (node (ref "U7") (pin "2") (pinfunction "3VO_2") (pintype "bidirectional"))
    )
    (net (code "64") (name "unconnected-(U7-GND2-Pad12)") (class "Default")
      (node (ref "U7") (pin "12") (pinfunction "GND2_12") (pintype "bidirectional"))
    )
    (net (code "65") (name "unconnected-(U7-PPS-Pad11)") (class "Default")
      (node (ref "U7") (pin "11") (pinfunction "PPS_11") (pintype "bidirectional"))
    )
    (net (code "66") (name "unconnected-(U7-RXI-Pad9)") (class "Default")
      (node (ref "U7") (pin "9") (pinfunction "RXI_9") (pintype "bidirectional"))
    )
    (net (code "67") (name "unconnected-(U7-TXO-Pad8)") (class "Default")
      (node (ref "U7") (pin "8") (pinfunction "TXO_8") (pintype "bidirectional"))
    )
    (net (code "68") (name "unconnected-(U7-VIN2-Pad10)") (class "Default")
      (node (ref "U7") (pin "10") (pinfunction "VIN2_10") (pintype "bidirectional"))
    )
    (net (code "69") (name "unconnected-(U7-WAKE-Pad7)") (class "Default")
      (node (ref "U7") (pin "7") (pinfunction "WAKE_7") (pintype "bidirectional"))
    )
  )
)
